# power_1.net
KiCad netlist of a schematic drawn in EAGLE
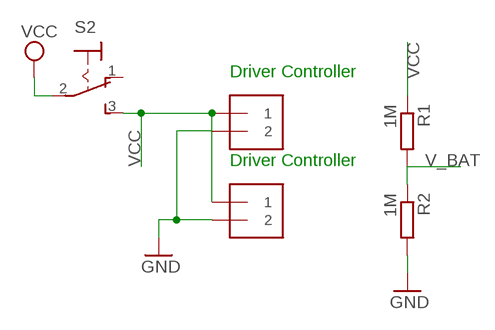
[diagram p0: schematic, sheet 1]

(export (version "E")
  (design (tool "Eeschema 10.0.6"))
  (components
    (comp (ref "J1")
      (value "1X2-3.5MM")
      (footprint "eagle-import:1X2-3.5MM")
      (libsource (lib "eagle-import") (part "1X2-3.5MM"))
    )
    (comp (ref "J2")
      (value "1X2-3.5MM")
      (footprint "eagle-import:1X2-3.5MM")
      (libsource (lib "eagle-import") (part "1X2-3.5MM"))
    )
    (comp (ref "R1")
      (value "1M")
      (footprint "eagle-import:0204_7")
      (libsource (lib "eagle-import") (part "R0204/7"))
    )
    (comp (ref "R2")
      (value "1M")
      (footprint "eagle-import:0204_7")
      (libsource (lib "eagle-import") (part "R0204/7"))
    )
    (comp (ref "S2")
      (value "320-916")
      (footprint "eagle-import:320-916")
      (libsource (lib "eagle-import") (part "320-916"))
    )
  )
  (nets
    (net (code "1") (name "/V_BAT") (class "Default")
      (node (ref "R1") (pin "2") (pinfunction "2_2") (pintype "passive"))
      (node (ref "R2") (pin "1") (pinfunction "1_1") (pintype "passive"))
    )
    (net (code "2") (name "GND") (class "Default")
      (node (ref "J1") (pin "2") (pinfunction "2_2") (pintype "passive"))
      (node (ref "J2") (pin "2") (pinfunction "2_2") (pintype "passive"))
      (node (ref "R2") (pin "2") (pinfunction "2_2") (pintype "passive"))
    )
    (net (code "3") (name "VCC") (class "Default")
      (node (ref "J1") (pin "1") (pinfunction "1_1") (pintype "passive"))
      (node (ref "J2") (pin "1") (pinfunction "1_1") (pintype "passive"))
      (node (ref "R1") (pin "1") (pinfunction "1_1") (pintype "passive"))
      (node (ref "S2") (pin "2") (pinfunction "P_2") (pintype "passive"))
      (node (ref "S2") (pin "3") (pinfunction "S_3") (pintype "passive"))
    )
    (net (code "4") (name "unconnected-(S2-O-Pad1)") (class "Default")
      (node (ref "S2") (pin "1") (pinfunction "O_1") (pintype "passive"))
    )
  )
)
